# PrototypeV3.net
KiCad netlist of a schematic drawn in Altium Designer
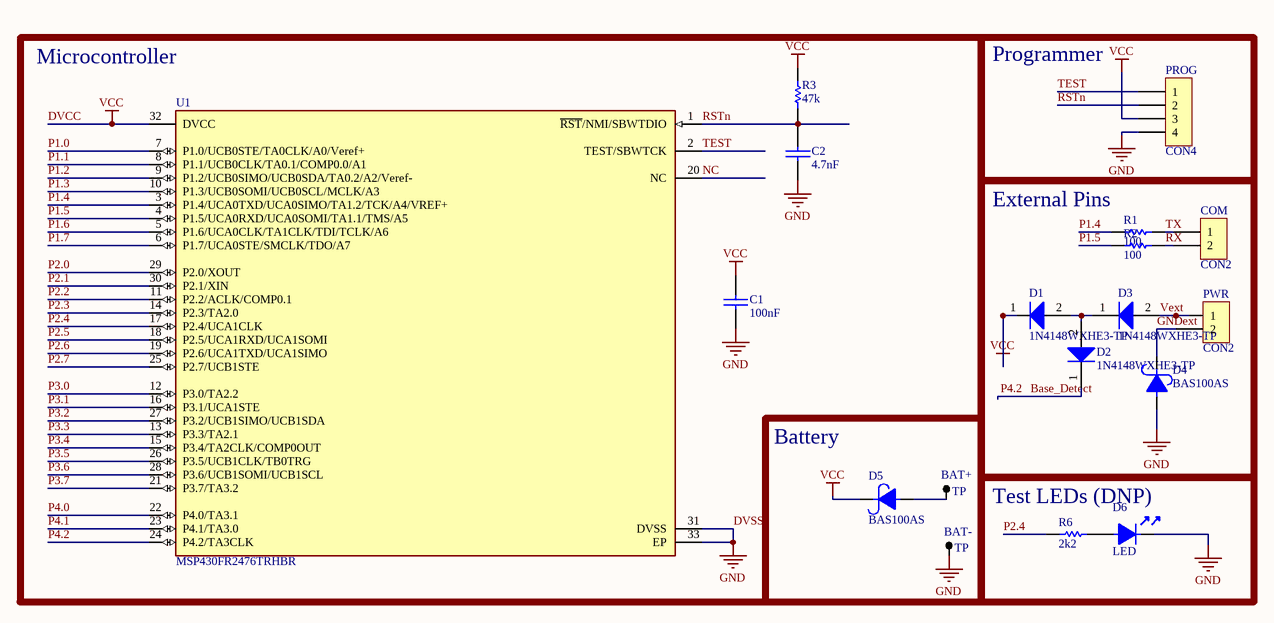
[diagram p0: PrototypeV3.SchDoc]

(export (version "E")
  (design (tool "Eeschema 10.0.6"))
  (components
    (comp (ref "BAT+") (value "TP") (footprint "TPTH") (libsource (lib "LIBEBAL") (part "TP")))
    (comp (ref "BAT-") (value "TP") (footprint "TPTH") (libsource (lib "LIBEBAL") (part "TP")))
    (comp (ref "C1") (value "100nF") (footprint "0805") (libsource (lib "LIBEBAL") (part "CAP")))
    (comp (ref "C2") (value "4.7nF") (footprint "0805") (libsource (lib "LIBEBAL") (part "CAP")))
    (comp (ref "COM") (value "CON2") (footprint "SIP2") (libsource (lib "LIBEBAL") (part "CON2")))
    (comp (ref "D1")
      (value "1N4148WXHE3-TP")
      (footprint "ONSC-SOD-123-2-425-04_V")
      (description "Switching Diode, 2-Pin SOD-123, Pb-Free, Tape and Reel")
      (fields (field (name "PARTNUMBER") "MMSD4148T1G") (field (name "MANUFACTURER") "On Semiconductor"))
      (libsource (lib "Altium Content Vault") (part "ONSC-D-K1A2-2"))
    )
    (comp (ref "D2")
      (value "1N4148WXHE3-TP")
      (footprint "ONSC-SOD-123-2-425-04_V")
      (description "Switching Diode, 2-Pin SOD-123, Pb-Free, Tape and Reel")
      (fields (field (name "PARTNUMBER") "MMSD4148T1G") (field (name "MANUFACTURER") "On Semiconductor"))
      (libsource (lib "Altium Content Vault") (part "ONSC-D-K1A2-2"))
    )
    (comp (ref "D3")
      (value "1N4148WXHE3-TP")
      (footprint "ONSC-SOD-123-2-425-04_V")
      (description "Switching Diode, 2-Pin SOD-123, Pb-Free, Tape and Reel")
      (fields (field (name "PARTNUMBER") "MMSD4148T1G") (field (name "MANUFACTURER") "On Semiconductor"))
      (libsource (lib "Altium Content Vault") (part "ONSC-D-K1A2-2"))
    )
    (comp (ref "D4")
      (value "BAS100AS")
      (footprint "SODFL350X110-2N")
      (libsource (lib "LIBEBAL") (part "DIODO SCHOTTKY"))
    )
    (comp (ref "D5")
      (value "BAS100AS")
      (footprint "SODFL350X110-2N")
      (libsource (lib "LIBEBAL") (part "DIODO SCHOTTKY"))
    )
    (comp (ref "D6") (value "LED") (footprint "0805") (libsource (lib "LIBEBAL Tobi") (part "LED")))
    (comp (ref "PROG") (value "CON4") (footprint "SIP4") (libsource (lib "LIBEBAL") (part "CON4")))
    (comp (ref "PWR") (value "CON2") (footprint "SIP2") (libsource (lib "LIBEBAL") (part "CON2")))
    (comp (ref "R1") (value "100") (footprint "0805") (libsource (lib "LIBEBAL") (part "RES")))
    (comp (ref "R2") (value "100") (footprint "0805") (libsource (lib "LIBEBAL") (part "RES")))
    (comp (ref "R3") (value "47k") (footprint "0805") (libsource (lib "LIBEBAL") (part "RES")))
    (comp (ref "R6") (value "2k2") (footprint "0805") (libsource (lib "LIBEBAL") (part "RES")))
    (comp (ref "U1")
      (value "MSP430FR2476TRHBR")
      (footprint "FP-RHB0032E-IPC_A")
      (description "IC MCU 16BIT 64.5KB FRAM 32VQFN")
      (libsource (lib "Altium Content Vault") (part "0d2dbf59e938affcfd15988a6e728c5"))
    )
  )
  (nets
    (net (code "1") (name "/Base_Detect") (class "Default")
      (node (ref "D2") (pin "1") (pinfunction "K_1") (pintype "passive"))
      (node (ref "U1") (pin "24") (pinfunction "P4.2/TA3CLK_24") (pintype "bidirectional"))
    )
    (net (code "2") (name "/GNDext") (class "Default")
      (node (ref "D4") (pin "2") (pinfunction "2_2") (pintype "passive"))
      (node (ref "PWR") (pin "2") (pinfunction "2_2") (pintype "passive"))
    )
    (net (code "3") (name "/NC") (class "Default")
      (node (ref "U1") (pin "20") (pinfunction "NC_20") (pintype "passive"))
    )
    (net (code "4") (name "/P1.0") (class "Default")
      (node (ref "U1") (pin "7") (pinfunction "P1.0/UCB0STE/TA0CLK/A0/Veref+_7") (pintype "bidirectional"))
    )
    (net (code "5") (name "/P1.1") (class "Default")
      (node (ref "U1") (pin "8") (pinfunction "P1.1/UCB0CLK/TA0.1/COMP0.0/A1_8") (pintype "bidirectional"))
    )
    (net (code "6") (name "/P1.2") (class "Default")
      (node (ref "U1") (pin "9") (pinfunction "P1.2/UCB0SIMO/UCB0SDA/TA0.2/A2/Veref-_9") (pintype "bidirectional"))
    )
    (net (code "7") (name "/P1.3") (class "Default")
      (node (ref "U1") (pin "10") (pinfunction "P1.3/UCB0SOMI/UCB0SCL/MCLK/A3_10") (pintype "bidirectional"))
    )
    (net (code "8") (name "/P1.4") (class "Default")
      (node (ref "R1") (pin "1") (pinfunction "1_1") (pintype "passive"))
      (node (ref "U1") (pin "3") (pinfunction "P1.4/UCA0TXD/UCA0SIMO/TA1.2/TCK/A4/VREF+_3") (pintype "bidirectional"))
    )
    (net (code "9") (name "/P1.5") (class "Default")
      (node (ref "R2") (pin "2") (pinfunction "2_2") (pintype "passive"))
      (node (ref "U1") (pin "4") (pinfunction "P1.5/UCA0RXD/UCA0SOMI/TA1.1/TMS/A5_4") (pintype "bidirectional"))
    )
    (net (code "10") (name "/P1.6") (class "Default")
      (node (ref "U1") (pin "5") (pinfunction "P1.6/UCA0CLK/TA1CLK/TDI/TCLK/A6_5") (pintype "bidirectional"))
    )
    (net (code "11") (name "/P1.7") (class "Default")
      (node (ref "U1") (pin "6") (pinfunction "P1.7/UCA0STE/SMCLK/TDO/A7_6") (pintype "bidirectional"))
    )
    (net (code "12") (name "/P2.0") (class "Default")
      (node (ref "U1") (pin "29") (pinfunction "P2.0/XOUT_29") (pintype "bidirectional"))
    )
    (net (code "13") (name "/P2.1") (class "Default")
      (node (ref "U1") (pin "30") (pinfunction "P2.1/XIN_30") (pintype "bidirectional"))
    )
    (net (code "14") (name "/P2.2") (class "Default")
      (node (ref "U1") (pin "11") (pinfunction "P2.2/ACLK/COMP0.1_11") (pintype "bidirectional"))
    )
    (net (code "15") (name "/P2.3") (class "Default")
      (node (ref "U1") (pin "14") (pinfunction "P2.3/TA2.0_14") (pintype "bidirectional"))
    )
    (net (code "16") (name "/P2.4") (class "Default")
      (node (ref "R6") (pin "2") (pinfunction "2_2") (pintype "passive"))
      (node (ref "U1") (pin "17") (pinfunction "P2.4/UCA1CLK_17") (pintype "bidirectional"))
    )
    (net (code "17") (name "/P2.5") (class "Default")
      (node (ref "U1") (pin "18") (pinfunction "P2.5/UCA1RXD/UCA1SOMI_18") (pintype "bidirectional"))
    )
    (net (code "18") (name "/P2.6") (class "Default")
      (node (ref "U1") (pin "19") (pinfunction "P2.6/UCA1TXD/UCA1SIMO_19") (pintype "bidirectional"))
    )
    (net (code "19") (name "/P2.7") (class "Default")
      (node (ref "U1") (pin "25") (pinfunction "P2.7/UCB1STE_25") (pintype "bidirectional"))
    )
    (net (code "20") (name "/P3.0") (class "Default")
      (node (ref "U1") (pin "12") (pinfunction "P3.0/TA2.2_12") (pintype "bidirectional"))
    )
    (net (code "21") (name "/P3.1") (class "Default")
      (node (ref "U1") (pin "16") (pinfunction "P3.1/UCA1STE_16") (pintype "bidirectional"))
    )
    (net (code "22") (name "/P3.2") (class "Default")
      (node (ref "U1") (pin "27") (pinfunction "P3.2/UCB1SIMO/UCB1SDA_27") (pintype "bidirectional"))
    )
    (net (code "23") (name "/P3.3") (class "Default")
      (node (ref "U1") (pin "13") (pinfunction "P3.3/TA2.1_13") (pintype "bidirectional"))
    )
    (net (code "24") (name "/P3.4") (class "Default")
      (node (ref "U1") (pin "15") (pinfunction "P3.4/TA2CLK/COMP0OUT_15") (pintype "bidirectional"))
    )
    (net (code "25") (name "/P3.5") (class "Default")
      (node (ref "U1") (pin "26") (pinfunction "P3.5/UCB1CLK/TB0TRG_26") (pintype "bidirectional"))
    )
    (net (code "26") (name "/P3.6") (class "Default")
      (node (ref "U1") (pin "28") (pinfunction "P3.6/UCB1SOMI/UCB1SCL_28") (pintype "bidirectional"))
    )
    (net (code "27") (name "/P3.7") (class "Default")
      (node (ref "U1") (pin "21") (pinfunction "P3.7/TA3.2_21") (pintype "bidirectional"))
    )
    (net (code "28") (name "/P4.0") (class "Default")
      (node (ref "U1") (pin "22") (pinfunction "P4.0/TA3.1_22") (pintype "bidirectional"))
    )
    (net (code "29") (name "/P4.1") (class "Default")
      (node (ref "U1") (pin "23") (pinfunction "P4.1/TA3.0_23") (pintype "bidirectional"))
    )
    (net (code "30") (name "/RSTn") (class "Default")
      (node (ref "C2") (pin "1") (pinfunction "1_1") (pintype "passive"))
      (node (ref "PROG") (pin "2") (pinfunction "2_2") (pintype "passive"))
      (node (ref "R3") (pin "2") (pinfunction "2_2") (pintype "passive"))
      (node (ref "U1") (pin "1") (pinfunction "~{RST}/NMI/SBWTDIO_1") (pintype "input"))
    )
    (net (code "31") (name "/RX") (class "Default")
      (node (ref "COM") (pin "2") (pinfunction "2_2") (pintype "passive"))
      (node (ref "R2") (pin "1") (pinfunction "1_1") (pintype "passive"))
    )
    (net (code "32") (name "/TEST") (class "Default")
      (node (ref "PROG") (pin "1") (pinfunction "1_1") (pintype "passive"))
      (node (ref "U1") (pin "2") (pinfunction "TEST/SBWTCK_2") (pintype "passive"))
    )
    (net (code "33") (name "/TX") (class "Default")
      (node (ref "COM") (pin "1") (pinfunction "1_1") (pintype "passive"))
      (node (ref "R1") (pin "2") (pinfunction "2_2") (pintype "passive"))
    )
    (net (code "34") (name "/Vext") (class "Default")
      (node (ref "D3") (pin "2") (pinfunction "A_2") (pintype "passive"))
      (node (ref "PWR") (pin "1") (pinfunction "1_1") (pintype "passive"))
    )
    (net (code "35") (name "GND") (class "Default")
      (node (ref "BAT-") (pin "1") (pinfunction "1_1") (pintype "passive"))
      (node (ref "C1") (pin "2") (pinfunction "2_2") (pintype "passive"))
      (node (ref "C2") (pin "2") (pinfunction "2_2") (pintype "passive"))
      (node (ref "D4") (pin "1") (pinfunction "1_1") (pintype "passive"))
      (node (ref "D6") (pin "2") (pinfunction "2_2") (pintype "passive"))
      (node (ref "PROG") (pin "4") (pinfunction "4_4") (pintype "passive"))
      (node (ref "U1") (pin "31") (pinfunction "DVSS_31") (pintype "power_in"))
      (node (ref "U1") (pin "33") (pinfunction "EP_33") (pintype "power_in"))
    )
    (net (code "36") (name "Net-(BAT+-Pad1)") (class "Default")
      (node (ref "BAT+") (pin "1") (pinfunction "1_1") (pintype "passive"))
      (node (ref "D5") (pin "1") (pinfunction "1_1") (pintype "passive"))
    )
    (net (code "37") (name "Net-(D1-A)") (class "Default")
      (node (ref "D1") (pin "2") (pinfunction "A_2") (pintype "passive"))
      (node (ref "D2") (pin "2") (pinfunction "A_2") (pintype "passive"))
      (node (ref "D3") (pin "1") (pinfunction "K_1") (pintype "passive"))
    )
    (net (code "38") (name "Net-(D6-Pad1)") (class "Default")
      (node (ref "D6") (pin "1") (pinfunction "1_1") (pintype "passive"))
      (node (ref "R6") (pin "1") (pinfunction "1_1") (pintype "passive"))
    )
    (net (code "39") (name "VCC") (class "Default")
      (node (ref "C1") (pin "1") (pinfunction "1_1") (pintype "passive"))
      (node (ref "D1") (pin "1") (pinfunction "K_1") (pintype "passive"))
      (node (ref "D5") (pin "2") (pinfunction "2_2") (pintype "passive"))
      (node (ref "PROG") (pin "3") (pinfunction "3_3") (pintype "passive"))
      (node (ref "R3") (pin "1") (pinfunction "1_1") (pintype "passive"))
      (node (ref "U1") (pin "32") (pinfunction "DVCC_32") (pintype "power_in"))
    )
  )
)
